# Sheet2.net
KiCad netlist of a schematic drawn in Altium Designer
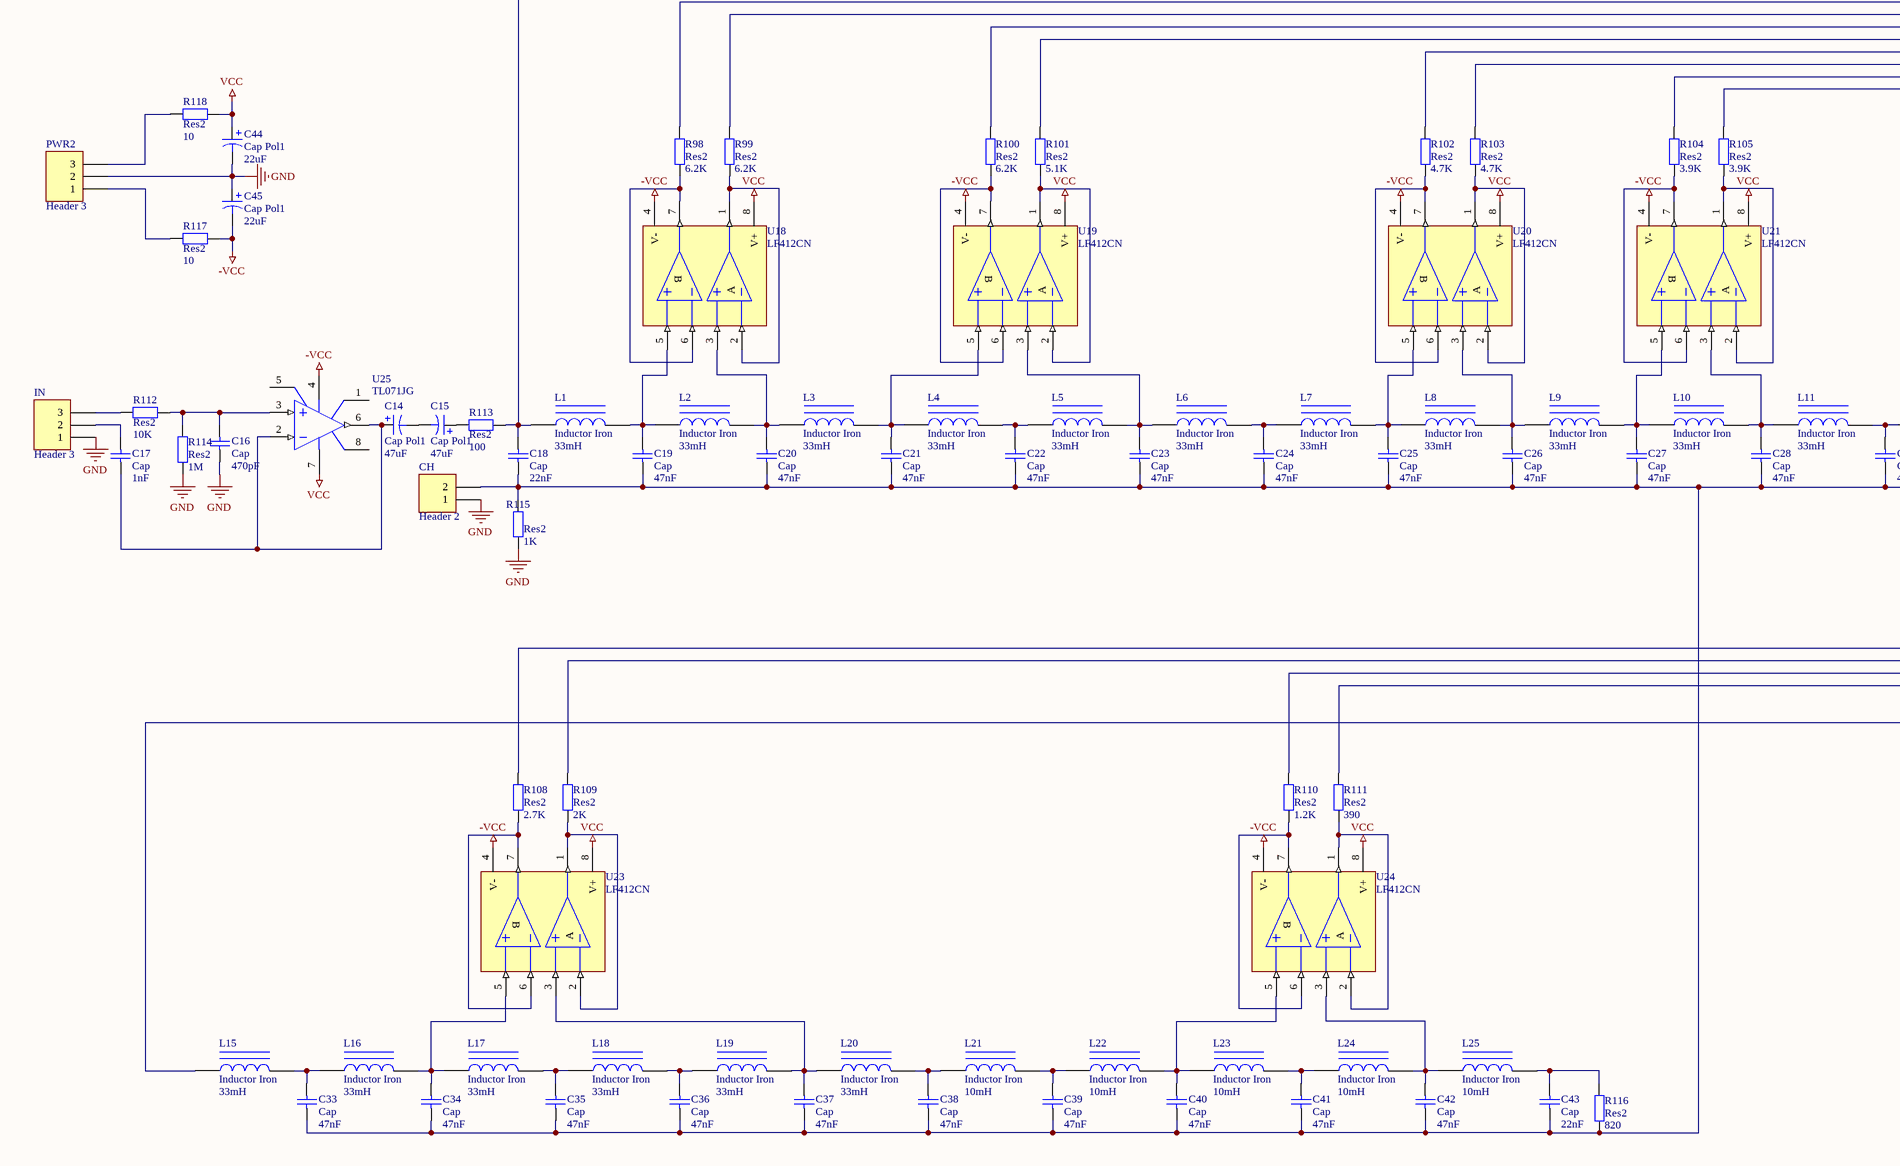
[diagram p0: Sheet2.SchDoc, left]
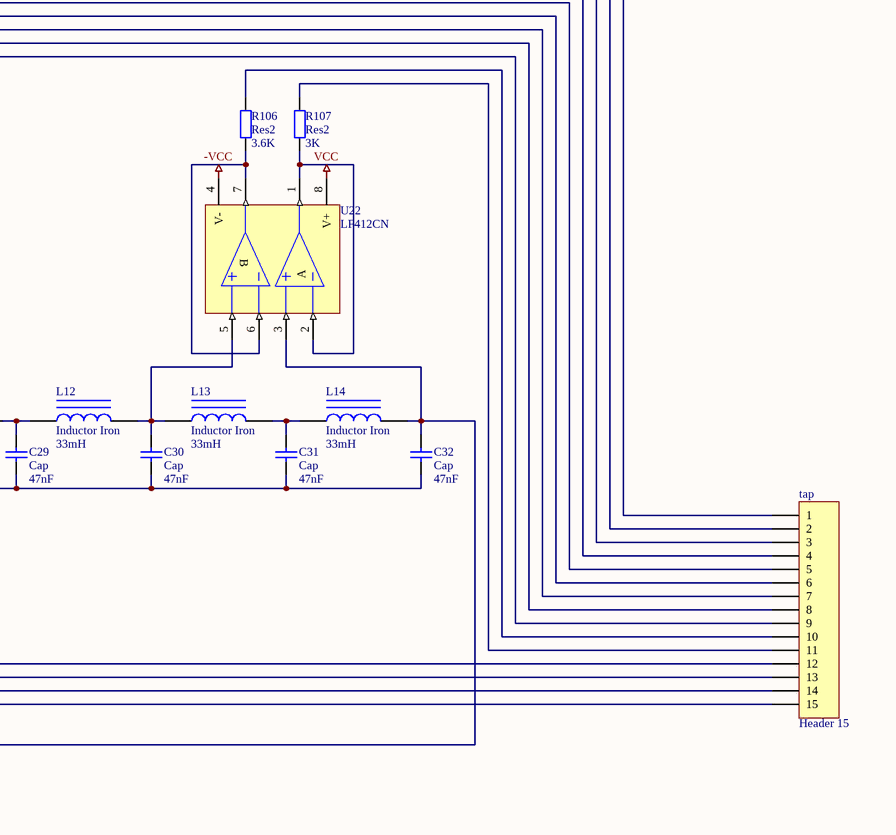
[diagram p1: Sheet2.SchDoc, right]

(export (version "E")
  (design (tool "Eeschema 10.0.6"))
  (components
    (comp (ref "C14")
      (value "Cap Pol1")
      (footprint "B")
      (description "Polarized Capacitor (Radial)")
      (fields (field (name "ALTIUM_VALUE") "47uF") (field (name "PUBLISHER") "Altium Limited"))
      (libsource (lib "Miscellaneous Devices") (part "Cap Pol1"))
    )
    (comp (ref "C15")
      (value "Cap Pol1")
      (footprint "B")
      (description "Polarized Capacitor (Radial)")
      (fields (field (name "ALTIUM_VALUE") "47uF") (field (name "PUBLISHER") "Altium Limited"))
      (libsource (lib "Miscellaneous Devices") (part "Cap Pol1"))
    )
    (comp (ref "C16")
      (value "Cap")
      (footprint "VP45-3.2")
      (description "Capacitor")
      (fields (field (name "ALTIUM_VALUE") "470pF") (field (name "PUBLISHER") "Altium Limited"))
      (libsource (lib "Miscellaneous Devices") (part "Cap"))
    )
    (comp (ref "C17")
      (value "Cap")
      (footprint "VP45-3.2")
      (description "Capacitor")
      (fields (field (name "ALTIUM_VALUE") "1nF") (field (name "PUBLISHER") "Altium Limited"))
      (libsource (lib "Miscellaneous Devices") (part "Cap"))
    )
    (comp (ref "C18")
      (value "Cap")
      (footprint "VP45-3.2")
      (description "Capacitor")
      (fields (field (name "ALTIUM_VALUE") "22nF") (field (name "PUBLISHER") "Altium Limited"))
      (libsource (lib "Miscellaneous Devices") (part "Cap"))
    )
    (comp (ref "C19")
      (value "Cap")
      (footprint "VP45-3.2")
      (description "Capacitor")
      (fields (field (name "ALTIUM_VALUE") "47nF") (field (name "PUBLISHER") "Altium Limited"))
      (libsource (lib "Miscellaneous Devices") (part "Cap"))
    )
    (comp (ref "C20")
      (value "Cap")
      (footprint "VP45-3.2")
      (description "Capacitor")
      (fields (field (name "ALTIUM_VALUE") "47nF") (field (name "PUBLISHER") "Altium Limited"))
      (libsource (lib "Miscellaneous Devices") (part "Cap"))
    )
    (comp (ref "C21")
      (value "Cap")
      (footprint "VP45-3.2")
      (description "Capacitor")
      (fields (field (name "ALTIUM_VALUE") "47nF") (field (name "PUBLISHER") "Altium Limited"))
      (libsource (lib "Miscellaneous Devices") (part "Cap"))
    )
    (comp (ref "C22")
      (value "Cap")
      (footprint "VP45-3.2")
      (description "Capacitor")
      (fields (field (name "ALTIUM_VALUE") "47nF") (field (name "PUBLISHER") "Altium Limited"))
      (libsource (lib "Miscellaneous Devices") (part "Cap"))
    )
    (comp (ref "C23")
      (value "Cap")
      (footprint "VP45-3.2")
      (description "Capacitor")
      (fields (field (name "ALTIUM_VALUE") "47nF") (field (name "PUBLISHER") "Altium Limited"))
      (libsource (lib "Miscellaneous Devices") (part "Cap"))
    )
    (comp (ref "C24")
      (value "Cap")
      (footprint "VP45-3.2")
      (description "Capacitor")
      (fields (field (name "ALTIUM_VALUE") "47nF") (field (name "PUBLISHER") "Altium Limited"))
      (libsource (lib "Miscellaneous Devices") (part "Cap"))
    )
    (comp (ref "C25")
      (value "Cap")
      (footprint "VP45-3.2")
      (description "Capacitor")
      (fields (field (name "ALTIUM_VALUE") "47nF") (field (name "PUBLISHER") "Altium Limited"))
      (libsource (lib "Miscellaneous Devices") (part "Cap"))
    )
    (comp (ref "C26")
      (value "Cap")
      (footprint "VP45-3.2")
      (description "Capacitor")
      (fields (field (name "ALTIUM_VALUE") "47nF") (field (name "PUBLISHER") "Altium Limited"))
      (libsource (lib "Miscellaneous Devices") (part "Cap"))
    )
    (comp (ref "C27")
      (value "Cap")
      (footprint "VP45-3.2")
      (description "Capacitor")
      (fields (field (name "ALTIUM_VALUE") "47nF") (field (name "PUBLISHER") "Altium Limited"))
      (libsource (lib "Miscellaneous Devices") (part "Cap"))
    )
    (comp (ref "C28")
      (value "Cap")
      (footprint "VP45-3.2")
      (description "Capacitor")
      (fields (field (name "ALTIUM_VALUE") "47nF") (field (name "PUBLISHER") "Altium Limited"))
      (libsource (lib "Miscellaneous Devices") (part "Cap"))
    )
    (comp (ref "C29")
      (value "Cap")
      (footprint "VP45-3.2")
      (description "Capacitor")
      (fields (field (name "ALTIUM_VALUE") "47nF") (field (name "PUBLISHER") "Altium Limited"))
      (libsource (lib "Miscellaneous Devices") (part "Cap"))
    )
    (comp (ref "C30")
      (value "Cap")
      (footprint "VP45-3.2")
      (description "Capacitor")
      (fields (field (name "ALTIUM_VALUE") "47nF") (field (name "PUBLISHER") "Altium Limited"))
      (libsource (lib "Miscellaneous Devices") (part "Cap"))
    )
    (comp (ref "C31")
      (value "Cap")
      (footprint "VP45-3.2")
      (description "Capacitor")
      (fields (field (name "ALTIUM_VALUE") "47nF") (field (name "PUBLISHER") "Altium Limited"))
      (libsource (lib "Miscellaneous Devices") (part "Cap"))
    )
    (comp (ref "C32")
      (value "Cap")
      (footprint "VP45-3.2")
      (description "Capacitor")
      (fields (field (name "ALTIUM_VALUE") "47nF") (field (name "PUBLISHER") "Altium Limited"))
      (libsource (lib "Miscellaneous Devices") (part "Cap"))
    )
    (comp (ref "C33")
      (value "Cap")
      (footprint "VP45-3.2")
      (description "Capacitor")
      (fields (field (name "ALTIUM_VALUE") "47nF") (field (name "PUBLISHER") "Altium Limited"))
      (libsource (lib "Miscellaneous Devices") (part "Cap"))
    )
    (comp (ref "C34")
      (value "Cap")
      (footprint "VP45-3.2")
      (description "Capacitor")
      (fields (field (name "ALTIUM_VALUE") "47nF") (field (name "PUBLISHER") "Altium Limited"))
      (libsource (lib "Miscellaneous Devices") (part "Cap"))
    )
    (comp (ref "C35")
      (value "Cap")
      (footprint "VP45-3.2")
      (description "Capacitor")
      (fields (field (name "ALTIUM_VALUE") "47nF") (field (name "PUBLISHER") "Altium Limited"))
      (libsource (lib "Miscellaneous Devices") (part "Cap"))
    )
    (comp (ref "C36")
      (value "Cap")
      (footprint "VP45-3.2")
      (description "Capacitor")
      (fields (field (name "ALTIUM_VALUE") "47nF") (field (name "PUBLISHER") "Altium Limited"))
      (libsource (lib "Miscellaneous Devices") (part "Cap"))
    )
    (comp (ref "C37")
      (value "Cap")
      (footprint "VP45-3.2")
      (description "Capacitor")
      (fields (field (name "ALTIUM_VALUE") "47nF") (field (name "PUBLISHER") "Altium Limited"))
      (libsource (lib "Miscellaneous Devices") (part "Cap"))
    )
    (comp (ref "C38")
      (value "Cap")
      (footprint "VP45-3.2")
      (description "Capacitor")
      (fields (field (name "ALTIUM_VALUE") "47nF") (field (name "PUBLISHER") "Altium Limited"))
      (libsource (lib "Miscellaneous Devices") (part "Cap"))
    )
    (comp (ref "C39")
      (value "Cap")
      (footprint "VP45-3.2")
      (description "Capacitor")
      (fields (field (name "ALTIUM_VALUE") "47nF") (field (name "PUBLISHER") "Altium Limited"))
      (libsource (lib "Miscellaneous Devices") (part "Cap"))
    )
    (comp (ref "C40")
      (value "Cap")
      (footprint "VP45-3.2")
      (description "Capacitor")
      (fields (field (name "ALTIUM_VALUE") "47nF") (field (name "PUBLISHER") "Altium Limited"))
      (libsource (lib "Miscellaneous Devices") (part "Cap"))
    )
    (comp (ref "C41")
      (value "Cap")
      (footprint "VP45-3.2")
      (description "Capacitor")
      (fields (field (name "ALTIUM_VALUE") "47nF") (field (name "PUBLISHER") "Altium Limited"))
      (libsource (lib "Miscellaneous Devices") (part "Cap"))
    )
    (comp (ref "C42")
      (value "Cap")
      (footprint "VP45-3.2")
      (description "Capacitor")
      (fields (field (name "ALTIUM_VALUE") "47nF") (field (name "PUBLISHER") "Altium Limited"))
      (libsource (lib "Miscellaneous Devices") (part "Cap"))
    )
    (comp (ref "C43")
      (value "Cap")
      (footprint "VP45-3.2")
      (description "Capacitor")
      (fields (field (name "ALTIUM_VALUE") "22nF") (field (name "PUBLISHER") "Altium Limited"))
      (libsource (lib "Miscellaneous Devices") (part "Cap"))
    )
    (comp (ref "C44")
      (value "Cap Pol1")
      (footprint "B")
      (description "Polarized Capacitor (Radial)")
      (fields (field (name "ALTIUM_VALUE") "22uF") (field (name "PUBLISHER") "Altium Limited"))
      (libsource (lib "Miscellaneous Devices") (part "Cap Pol1"))
    )
    (comp (ref "C45")
      (value "Cap Pol1")
      (footprint "B")
      (description "Polarized Capacitor (Radial)")
      (fields (field (name "ALTIUM_VALUE") "22uF") (field (name "PUBLISHER") "Altium Limited"))
      (libsource (lib "Miscellaneous Devices") (part "Cap Pol1"))
    )
    (comp (ref "CH")
      (value "Header 2")
      (footprint "HDR1X2")
      (description "Header, 2-Pin")
      (fields (field (name "PUBLISHER") "Altium Limited"))
      (libsource (lib "Miscellaneous Connectors") (part "Header 2"))
    )
    (comp (ref "IN")
      (value "Header 3")
      (footprint "HDR1X3")
      (description "Header, 3-Pin")
      (fields (field (name "PUBLISHER") "Altium Limited"))
      (libsource (lib "Miscellaneous Connectors") (part "Header 3"))
    )
    (comp (ref "L1")
      (value "Inductor Iron")
      (footprint "AXIAL-0.9")
      (description "Magnetic-Core Inductor")
      (fields (field (name "ALTIUM_VALUE") "33mH") (field (name "PUBLISHER") "Altium Limited"))
      (libsource (lib "Miscellaneous Devices") (part "Inductor Iron"))
    )
    (comp (ref "L2")
      (value "Inductor Iron")
      (footprint "AXIAL-0.9")
      (description "Magnetic-Core Inductor")
      (fields (field (name "ALTIUM_VALUE") "33mH") (field (name "PUBLISHER") "Altium Limited"))
      (libsource (lib "Miscellaneous Devices") (part "Inductor Iron"))
    )
    (comp (ref "L3")
      (value "Inductor Iron")
      (footprint "AXIAL-0.9")
      (description "Magnetic-Core Inductor")
      (fields (field (name "ALTIUM_VALUE") "33mH") (field (name "PUBLISHER") "Altium Limited"))
      (libsource (lib "Miscellaneous Devices") (part "Inductor Iron"))
    )
    (comp (ref "L4")
      (value "Inductor Iron")
      (footprint "AXIAL-0.9")
      (description "Magnetic-Core Inductor")
      (fields (field (name "ALTIUM_VALUE") "33mH") (field (name "PUBLISHER") "Altium Limited"))
      (libsource (lib "Miscellaneous Devices") (part "Inductor Iron"))
    )
    (comp (ref "L5")
      (value "Inductor Iron")
      (footprint "AXIAL-0.9")
      (description "Magnetic-Core Inductor")
      (fields (field (name "ALTIUM_VALUE") "33mH") (field (name "PUBLISHER") "Altium Limited"))
      (libsource (lib "Miscellaneous Devices") (part "Inductor Iron"))
    )
    (comp (ref "L6")
      (value "Inductor Iron")
      (footprint "AXIAL-0.9")
      (description "Magnetic-Core Inductor")
      (fields (field (name "ALTIUM_VALUE") "33mH") (field (name "PUBLISHER") "Altium Limited"))
      (libsource (lib "Miscellaneous Devices") (part "Inductor Iron"))
    )
    (comp (ref "L7")
      (value "Inductor Iron")
      (footprint "AXIAL-0.9")
      (description "Magnetic-Core Inductor")
      (fields (field (name "ALTIUM_VALUE") "33mH") (field (name "PUBLISHER") "Altium Limited"))
      (libsource (lib "Miscellaneous Devices") (part "Inductor Iron"))
    )
    (comp (ref "L8")
      (value "Inductor Iron")
      (footprint "AXIAL-0.9")
      (description "Magnetic-Core Inductor")
      (fields (field (name "ALTIUM_VALUE") "33mH") (field (name "PUBLISHER") "Altium Limited"))
      (libsource (lib "Miscellaneous Devices") (part "Inductor Iron"))
    )
    (comp (ref "L9")
      (value "Inductor Iron")
      (footprint "AXIAL-0.9")
      (description "Magnetic-Core Inductor")
      (fields (field (name "ALTIUM_VALUE") "33mH") (field (name "PUBLISHER") "Altium Limited"))
      (libsource (lib "Miscellaneous Devices") (part "Inductor Iron"))
    )
    (comp (ref "L10")
      (value "Inductor Iron")
      (footprint "AXIAL-0.9")
      (description "Magnetic-Core Inductor")
      (fields (field (name "ALTIUM_VALUE") "33mH") (field (name "PUBLISHER") "Altium Limited"))
      (libsource (lib "Miscellaneous Devices") (part "Inductor Iron"))
    )
    (comp (ref "L11")
      (value "Inductor Iron")
      (footprint "AXIAL-0.9")
      (description "Magnetic-Core Inductor")
      (fields (field (name "ALTIUM_VALUE") "33mH") (field (name "PUBLISHER") "Altium Limited"))
      (libsource (lib "Miscellaneous Devices") (part "Inductor Iron"))
    )
    (comp (ref "L12")
      (value "Inductor Iron")
      (footprint "AXIAL-0.9")
      (description "Magnetic-Core Inductor")
      (fields (field (name "ALTIUM_VALUE") "33mH") (field (name "PUBLISHER") "Altium Limited"))
      (libsource (lib "Miscellaneous Devices") (part "Inductor Iron"))
    )
    (comp (ref "L13")
      (value "Inductor Iron")
      (footprint "AXIAL-0.9")
      (description "Magnetic-Core Inductor")
      (fields (field (name "ALTIUM_VALUE") "33mH") (field (name "PUBLISHER") "Altium Limited"))
      (libsource (lib "Miscellaneous Devices") (part "Inductor Iron"))
    )
    (comp (ref "L14")
      (value "Inductor Iron")
      (footprint "AXIAL-0.9")
      (description "Magnetic-Core Inductor")
      (fields (field (name "ALTIUM_VALUE") "33mH") (field (name "PUBLISHER") "Altium Limited"))
      (libsource (lib "Miscellaneous Devices") (part "Inductor Iron"))
    )
    (comp (ref "L15")
      (value "Inductor Iron")
      (footprint "AXIAL-0.9")
      (description "Magnetic-Core Inductor")
      (fields (field (name "ALTIUM_VALUE") "33mH") (field (name "PUBLISHER") "Altium Limited"))
      (libsource (lib "Miscellaneous Devices") (part "Inductor Iron"))
    )
    (comp (ref "L16")
      (value "Inductor Iron")
      (footprint "AXIAL-0.9")
      (description "Magnetic-Core Inductor")
      (fields (field (name "ALTIUM_VALUE") "33mH") (field (name "PUBLISHER") "Altium Limited"))
      (libsource (lib "Miscellaneous Devices") (part "Inductor Iron"))
    )
    (comp (ref "L17")
      (value "Inductor Iron")
      (footprint "AXIAL-0.9")
      (description "Magnetic-Core Inductor")
      (fields (field (name "ALTIUM_VALUE") "33mH") (field (name "PUBLISHER") "Altium Limited"))
      (libsource (lib "Miscellaneous Devices") (part "Inductor Iron"))
    )
    (comp (ref "L18")
      (value "Inductor Iron")
      (footprint "AXIAL-0.9")
      (description "Magnetic-Core Inductor")
      (fields (field (name "ALTIUM_VALUE") "33mH") (field (name "PUBLISHER") "Altium Limited"))
      (libsource (lib "Miscellaneous Devices") (part "Inductor Iron"))
    )
    (comp (ref "L19")
      (value "Inductor Iron")
      (footprint "AXIAL-0.9")
      (description "Magnetic-Core Inductor")
      (fields (field (name "ALTIUM_VALUE") "33mH") (field (name "PUBLISHER") "Altium Limited"))
      (libsource (lib "Miscellaneous Devices") (part "Inductor Iron"))
    )
    (comp (ref "L20")
      (value "Inductor Iron")
      (footprint "AXIAL-0.9")
      (description "Magnetic-Core Inductor")
      (fields (field (name "ALTIUM_VALUE") "33mH") (field (name "PUBLISHER") "Altium Limited"))
      (libsource (lib "Miscellaneous Devices") (part "Inductor Iron"))
    )
    (comp (ref "L21")
      (value "Inductor Iron")
      (footprint "AXIAL-0.9")
      (description "Magnetic-Core Inductor")
      (fields (field (name "ALTIUM_VALUE") "10mH") (field (name "PUBLISHER") "Altium Limited"))
      (libsource (lib "Miscellaneous Devices") (part "Inductor Iron"))
    )
    (comp (ref "L22")
      (value "Inductor Iron")
      (footprint "AXIAL-0.9")
      (description "Magnetic-Core Inductor")
      (fields (field (name "ALTIUM_VALUE") "10mH") (field (name "PUBLISHER") "Altium Limited"))
      (libsource (lib "Miscellaneous Devices") (part "Inductor Iron"))
    )
    (comp (ref "L23")
      (value "Inductor Iron")
      (footprint "AXIAL-0.9")
      (description "Magnetic-Core Inductor")
      (fields (field (name "ALTIUM_VALUE") "10mH") (field (name "PUBLISHER") "Altium Limited"))
      (libsource (lib "Miscellaneous Devices") (part "Inductor Iron"))
    )
    (comp (ref "L24")
      (value "Inductor Iron")
      (footprint "AXIAL-0.9")
      (description "Magnetic-Core Inductor")
      (fields (field (name "ALTIUM_VALUE") "10mH") (field (name "PUBLISHER") "Altium Limited"))
      (libsource (lib "Miscellaneous Devices") (part "Inductor Iron"))
    )
    (comp (ref "L25")
      (value "Inductor Iron")
      (footprint "AXIAL-0.9")
      (description "Magnetic-Core Inductor")
      (fields (field (name "ALTIUM_VALUE") "10mH") (field (name "PUBLISHER") "Altium Limited"))
      (libsource (lib "Miscellaneous Devices") (part "Inductor Iron"))
    )
    (comp (ref "PWR2")
      (value "Header 3")
      (footprint "HDR1X3")
      (description "Header, 3-Pin")
      (fields (field (name "PUBLISHER") "Altium Limited"))
      (libsource (lib "Miscellaneous Connectors") (part "Header 3"))
    )
    (comp (ref "R98")
      (value "Res2")
      (footprint "AXIAL-0.4")
      (description "Resistor")
      (fields (field (name "ALTIUM_VALUE") "6.2K") (field (name "PUBLISHER") "Altium Limited"))
      (libsource (lib "") (part "Res2_1"))
    )
    (comp (ref "R99")
      (value "Res2")
      (footprint "AXIAL-0.4")
      (description "Resistor")
      (fields (field (name "ALTIUM_VALUE") "6.2K") (field (name "PUBLISHER") "Altium Limited"))
      (libsource (lib "") (part "Res2_1"))
    )
    (comp (ref "R100")
      (value "Res2")
      (footprint "AXIAL-0.4")
      (description "Resistor")
      (fields (field (name "ALTIUM_VALUE") "6.2K") (field (name "PUBLISHER") "Altium Limited"))
      (libsource (lib "") (part "Res2_1"))
    )
    (comp (ref "R101")
      (value "Res2")
      (footprint "AXIAL-0.4")
      (description "Resistor")
      (fields (field (name "ALTIUM_VALUE") "5.1K") (field (name "PUBLISHER") "Altium Limited"))
      (libsource (lib "") (part "Res2_1"))
    )
    (comp (ref "R102")
      (value "Res2")
      (footprint "AXIAL-0.4")
      (description "Resistor")
      (fields (field (name "ALTIUM_VALUE") "4.7K") (field (name "PUBLISHER") "Altium Limited"))
      (libsource (lib "") (part "Res2_1"))
    )
    (comp (ref "R103")
      (value "Res2")
      (footprint "AXIAL-0.4")
      (description "Resistor")
      (fields (field (name "ALTIUM_VALUE") "4.7K") (field (name "PUBLISHER") "Altium Limited"))
      (libsource (lib "") (part "Res2_1"))
    )
    (comp (ref "R104")
      (value "Res2")
      (footprint "AXIAL-0.4")
      (description "Resistor")
      (fields (field (name "ALTIUM_VALUE") "3.9K") (field (name "PUBLISHER") "Altium Limited"))
      (libsource (lib "") (part "Res2_1"))
    )
    (comp (ref "R105")
      (value "Res2")
      (footprint "AXIAL-0.4")
      (description "Resistor")
      (fields (field (name "ALTIUM_VALUE") "3.9K") (field (name "PUBLISHER") "Altium Limited"))
      (libsource (lib "") (part "Res2_1"))
    )
    (comp (ref "R106")
      (value "Res2")
      (footprint "AXIAL-0.4")
      (description "Resistor")
      (fields (field (name "ALTIUM_VALUE") "3.6K") (field (name "PUBLISHER") "Altium Limited"))
      (libsource (lib "") (part "Res2_1"))
    )
    (comp (ref "R107")
      (value "Res2")
      (footprint "AXIAL-0.4")
      (description "Resistor")
      (fields (field (name "ALTIUM_VALUE") "3K") (field (name "PUBLISHER") "Altium Limited"))
      (libsource (lib "") (part "Res2_1"))
    )
    (comp (ref "R108")
      (value "Res2")
      (footprint "AXIAL-0.4")
      (description "Resistor")
      (fields (field (name "ALTIUM_VALUE") "2.7K") (field (name "PUBLISHER") "Altium Limited"))
      (libsource (lib "") (part "Res2_1"))
    )
    (comp (ref "R109")
      (value "Res2")
      (footprint "AXIAL-0.4")
      (description "Resistor")
      (fields (field (name "ALTIUM_VALUE") "2K") (field (name "PUBLISHER") "Altium Limited"))
      (libsource (lib "") (part "Res2_1"))
    )
    (comp (ref "R110")
      (value "Res2")
      (footprint "AXIAL-0.4")
      (description "Resistor")
      (fields (field (name "ALTIUM_VALUE") "1.2K") (field (name "PUBLISHER") "Altium Limited"))
      (libsource (lib "") (part "Res2_1"))
    )
    (comp (ref "R111")
      (value "Res2")
      (footprint "AXIAL-0.4")
      (description "Resistor")
      (fields (field (name "ALTIUM_VALUE") "390") (field (name "PUBLISHER") "Altium Limited"))
      (libsource (lib "") (part "Res2_1"))
    )
    (comp (ref "R112")
      (value "Res2")
      (footprint "AXIAL-0.4")
      (description "Resistor")
      (fields (field (name "ALTIUM_VALUE") "10K") (field (name "PUBLISHER") "Altium Limited"))
      (libsource (lib "Miscellaneous Devices") (part "Res2"))
    )
    (comp (ref "R113")
      (value "Res2")
      (footprint "AXIAL-0.4")
      (description "Resistor")
      (fields (field (name "ALTIUM_VALUE") "100") (field (name "PUBLISHER") "Altium Limited"))
      (libsource (lib "") (part "Res2_2"))
    )
    (comp (ref "R114")
      (value "Res2")
      (footprint "AXIAL-0.4")
      (description "Resistor")
      (fields (field (name "ALTIUM_VALUE") "1M") (field (name "PUBLISHER") "Altium Limited"))
      (libsource (lib "") (part "Res2_1"))
    )
    (comp (ref "R115")
      (value "Res2")
      (footprint "AXIAL-0.4")
      (description "Resistor")
      (fields (field (name "ALTIUM_VALUE") "1K") (field (name "PUBLISHER") "Altium Limited"))
      (libsource (lib "") (part "Res2_1"))
    )
    (comp (ref "R116")
      (value "Res2")
      (footprint "AXIAL-0.4")
      (description "Resistor")
      (fields (field (name "ALTIUM_VALUE") "820") (field (name "PUBLISHER") "Altium Limited"))
      (libsource (lib "") (part "Res2_1"))
    )
    (comp (ref "R117")
      (value "Res2")
      (footprint "AXIAL-0.4")
      (description "Resistor")
      (fields (field (name "ALTIUM_VALUE") "10") (field (name "PUBLISHER") "Altium Limited"))
      (libsource (lib "Miscellaneous Devices") (part "Res2"))
    )
    (comp (ref "R118")
      (value "Res2")
      (footprint "AXIAL-0.4")
      (description "Resistor")
      (fields (field (name "ALTIUM_VALUE") "10") (field (name "PUBLISHER") "Altium Limited"))
      (libsource (lib "Miscellaneous Devices") (part "Res2"))
    )
    (comp (ref "tap")
      (value "Header 15")
      (footprint "HDR1X15")
      (description "Header, 15-Pin")
      (fields (field (name "PUBLISHER") "Altium Limited"))
      (libsource (lib "Miscellaneous Connectors") (part "Header 15"))
    )
    (comp (ref "U18")
      (value "LF412CN")
      (footprint "N08E")
      (description "Low Offset, Low Drift Dual JFET Input Operational Amplifier")
      (fields
        (field (name "MANUFACTURER") "National Semiconductor")
        (field (name "DIGIKEYPARTNUMBER") "LF412CN-ND")
        (field (name "PUBLISHER") "Altium Limited")
      )
      (libsource (lib "NSC Amplifier") (part "LF412CN"))
    )
    (comp (ref "U19")
      (value "LF412CN")
      (footprint "N08E")
      (description "Low Offset, Low Drift Dual JFET Input Operational Amplifier")
      (fields
        (field (name "MANUFACTURER") "National Semiconductor")
        (field (name "DIGIKEYPARTNUMBER") "LF412CN-ND")
        (field (name "PUBLISHER") "Altium Limited")
      )
      (libsource (lib "NSC Amplifier") (part "LF412CN"))
    )
    (comp (ref "U20")
      (value "LF412CN")
      (footprint "N08E")
      (description "Low Offset, Low Drift Dual JFET Input Operational Amplifier")
      (fields
        (field (name "MANUFACTURER") "National Semiconductor")
        (field (name "DIGIKEYPARTNUMBER") "LF412CN-ND")
        (field (name "PUBLISHER") "Altium Limited")
      )
      (libsource (lib "NSC Amplifier") (part "LF412CN"))
    )
    (comp (ref "U21")
      (value "LF412CN")
      (footprint "N08E")
      (description "Low Offset, Low Drift Dual JFET Input Operational Amplifier")
      (fields
        (field (name "MANUFACTURER") "National Semiconductor")
        (field (name "DIGIKEYPARTNUMBER") "LF412CN-ND")
        (field (name "PUBLISHER") "Altium Limited")
      )
      (libsource (lib "NSC Amplifier") (part "LF412CN"))
    )
    (comp (ref "U22")
      (value "LF412CN")
      (footprint "N08E")
      (description "Low Offset, Low Drift Dual JFET Input Operational Amplifier")
      (fields
        (field (name "MANUFACTURER") "National Semiconductor")
        (field (name "DIGIKEYPARTNUMBER") "LF412CN-ND")
        (field (name "PUBLISHER") "Altium Limited")
      )
      (libsource (lib "NSC Amplifier") (part "LF412CN"))
    )
    (comp (ref "U23")
      (value "LF412CN")
      (footprint "N08E")
      (description "Low Offset, Low Drift Dual JFET Input Operational Amplifier")
      (fields
        (field (name "MANUFACTURER") "National Semiconductor")
        (field (name "DIGIKEYPARTNUMBER") "LF412CN-ND")
        (field (name "PUBLISHER") "Altium Limited")
      )
      (libsource (lib "NSC Amplifier") (part "LF412CN"))
    )
    (comp (ref "U24")
      (value "LF412CN")
      (footprint "N08E")
      (description "Low Offset, Low Drift Dual JFET Input Operational Amplifier")
      (fields
        (field (name "MANUFACTURER") "National Semiconductor")
        (field (name "DIGIKEYPARTNUMBER") "LF412CN-ND")
        (field (name "PUBLISHER") "Altium Limited")
      )
      (libsource (lib "NSC Amplifier") (part "LF412CN"))
    )
    (comp (ref "U25")
      (value "TL071JG")
      (footprint "JG008")
      (description "Low-Noise JFET-Input Operational Amplifier")
      (fields (field (name "PUBLISHER") "Altium Limited"))
      (libsource (lib "TI Operational Amplifier") (part "TL071JG"))
    )
  )
  (nets
    (net (code "1") (name "-VCC") (class "Default")
      (node (ref "C45") (pin "2") (pinfunction "2_2") (pintype "passive"))
      (node (ref "R117") (pin "1") (pinfunction "1_1") (pintype "passive"))
      (node (ref "U18") (pin "4") (pinfunction "V-_4") (pintype "power_in"))
      (node (ref "U19") (pin "4") (pinfunction "V-_4") (pintype "power_in"))
      (node (ref "U20") (pin "4") (pinfunction "V-_4") (pintype "power_in"))
      (node (ref "U21") (pin "4") (pinfunction "V-_4") (pintype "power_in"))
      (node (ref "U22") (pin "4") (pinfunction "V-_4") (pintype "power_in"))
      (node (ref "U23") (pin "4") (pinfunction "V-_4") (pintype "power_in"))
      (node (ref "U24") (pin "4") (pinfunction "V-_4") (pintype "power_in"))
      (node (ref "U25") (pin "4") (pinfunction "V-_4") (pintype "power_in"))
    )
    (net (code "2") (name "GND") (class "Default")
      (node (ref "C16") (pin "1") (pinfunction "1_1") (pintype "passive"))
      (node (ref "C44") (pin "2") (pinfunction "2_2") (pintype "passive"))
      (node (ref "C45") (pin "1") (pinfunction "1_1") (pintype "passive"))
      (node (ref "CH") (pin "1") (pinfunction "1_1") (pintype "passive"))
      (node (ref "IN") (pin "1") (pinfunction "1_1") (pintype "passive"))
      (node (ref "PWR2") (pin "2") (pinfunction "2_2") (pintype "passive"))
      (node (ref "R114") (pin "1") (pinfunction "1_1") (pintype "passive"))
      (node (ref "R115") (pin "1") (pinfunction "1_1") (pintype "passive"))
    )
    (net (code "3") (name "Net-(C14-Pad2)") (class "Default")
      (node (ref "C14") (pin "2") (pinfunction "2_2") (pintype "passive"))
      (node (ref "C15") (pin "2") (pinfunction "2_2") (pintype "passive"))
    )
    (net (code "4") (name "Net-(C15-Pad1)") (class "Default")
      (node (ref "C15") (pin "1") (pinfunction "1_1") (pintype "passive"))
      (node (ref "R113") (pin "1") (pinfunction "1_1") (pintype "passive"))
    )
    (net (code "5") (name "Net-(C17-Pad2)") (class "Default")
      (node (ref "C17") (pin "2") (pinfunction "2_2") (pintype "passive"))
      (node (ref "IN") (pin "2") (pinfunction "2_2") (pintype "passive"))
    )
    (net (code "6") (name "Net-(C18-Pad1)") (class "Default")
      (node (ref "C18") (pin "1") (pinfunction "1_1") (pintype "passive"))
      (node (ref "C19") (pin "1") (pinfunction "1_1") (pintype "passive"))
      (node (ref "C20") (pin "1") (pinfunction "1_1") (pintype "passive"))
      (node (ref "C21") (pin "1") (pinfunction "1_1") (pintype "passive"))
      (node (ref "C22") (pin "1") (pinfunction "1_1") (pintype "passive"))
      (node (ref "C23") (pin "1") (pinfunction "1_1") (pintype "passive"))
      (node (ref "C24") (pin "1") (pinfunction "1_1") (pintype "passive"))
      (node (ref "C25") (pin "1") (pinfunction "1_1") (pintype "passive"))
      (node (ref "C26") (pin "1") (pinfunction "1_1") (pintype "passive"))
      (node (ref "C27") (pin "1") (pinfunction "1_1") (pintype "passive"))
      (node (ref "C28") (pin "1") (pinfunction "1_1") (pintype "passive"))
      (node (ref "C29") (pin "1") (pinfunction "1_1") (pintype "passive"))
      (node (ref "C30") (pin "1") (pinfunction "1_1") (pintype "passive"))
      (node (ref "C31") (pin "1") (pinfunction "1_1") (pintype "passive"))
      (node (ref "C32") (pin "1") (pinfunction "1_1") (pintype "passive"))
      (node (ref "C33") (pin "1") (pinfunction "1_1") (pintype "passive"))
      (node (ref "C34") (pin "1") (pinfunction "1_1") (pintype "passive"))
      (node (ref "C35") (pin "1") (pinfunction "1_1") (pintype "passive"))
      (node (ref "C36") (pin "1") (pinfunction "1_1") (pintype "passive"))
      (node (ref "C37") (pin "1") (pinfunction "1_1") (pintype "passive"))
      (node (ref "C38") (pin "1") (pinfunction "1_1") (pintype "passive"))
      (node (ref "C39") (pin "1") (pinfunction "1_1") (pintype "passive"))
      (node (ref "C40") (pin "1") (pinfunction "1_1") (pintype "passive"))
      (node (ref "C41") (pin "1") (pinfunction "1_1") (pintype "passive"))
      (node (ref "C42") (pin "1") (pinfunction "1_1") (pintype "passive"))
      (node (ref "C43") (pin "1") (pinfunction "1_1") (pintype "passive"))
      (node (ref "CH") (pin "2") (pinfunction "2_2") (pintype "passive"))
      (node (ref "R115") (pin "2") (pinfunction "2_2") (pintype "passive"))
      (node (ref "R116") (pin "1") (pinfunction "1_1") (pintype "passive"))
    )
    (net (code "7") (name "Net-(C18-Pad2)") (class "Default")
      (node (ref "C18") (pin "2") (pinfunction "2_2") (pintype "passive"))
      (node (ref "L1") (pin "1") (pinfunction "1_1") (pintype "passive"))
      (node (ref "R113") (pin "2") (pinfunction "2_2") (pintype "passive"))
      (node (ref "tap") (pin "1") (pinfunction "1_1") (pintype "passive"))
    )
    (net (code "8") (name "Net-(C22-Pad2)") (class "Default")
      (node (ref "C22") (pin "2") (pinfunction "2_2") (pintype "passive"))
      (node (ref "L4") (pin "2") (pinfunction "2_2") (pintype "passive"))
      (node (ref "L5") (pin "1") (pinfunction "1_1") (pintype "passive"))
    )
    (net (code "9") (name "Net-(C24-Pad2)") (class "Default")
      (node (ref "C24") (pin "2") (pinfunction "2_2") (pintype "passive"))
      (node (ref "L6") (pin "2") (pinfunction "2_2") (pintype "passive"))
      (node (ref "L7") (pin "1") (pinfunction "1_1") (pintype "passive"))
    )
    (net (code "10") (name "Net-(C29-Pad2)") (class "Default")
      (node (ref "C29") (pin "2") (pinfunction "2_2") (pintype "passive"))
      (node (ref "L11") (pin "2") (pinfunction "2_2") (pintype "passive"))
      (node (ref "L12") (pin "1") (pinfunction "1_1") (pintype "passive"))
    )
    (net (code "11") (name "Net-(C31-Pad2)") (class "Default")
      (node (ref "C31") (pin "2") (pinfunction "2_2") (pintype "passive"))
      (node (ref "L13") (pin "2") (pinfunction "2_2") (pintype "passive"))
      (node (ref "L14") (pin "1") (pinfunction "1_1") (pintype "passive"))
    )
    (net (code "12") (name "Net-(C33-Pad2)") (class "Default")
      (node (ref "C33") (pin "2") (pinfunction "2_2") (pintype "passive"))
      (node (ref "L15") (pin "2") (pinfunction "2_2") (pintype "passive"))
      (node (ref "L16") (pin "1") (pinfunction "1_1") (pintype "passive"))
    )
    (net (code "13") (name "Net-(C35-Pad2)") (class "Default")
      (node (ref "C35") (pin "2") (pinfunction "2_2") (pintype "passive"))
      (node (ref "L17") (pin "2") (pinfunction "2_2") (pintype "passive"))
      (node (ref "L18") (pin "1") (pinfunction "1_1") (pintype "passive"))
    )
    (net (code "14") (name "Net-(C36-Pad2)") (class "Default")
      (node (ref "C36") (pin "2") (pinfunction "2_2") (pintype "passive"))
      (node (ref "L18") (pin "2") (pinfunction "2_2") (pintype "passive"))
      (node (ref "L19") (pin "1") (pinfunction "1_1") (pintype "passive"))
    )
    (net (code "15") (name "Net-(C38-Pad2)") (class "Default")
      (node (ref "C38") (pin "2") (pinfunction "2_2") (pintype "passive"))
      (node (ref "L20") (pin "2") (pinfunction "2_2") (pintype "passive"))
      (node (ref "L21") (pin "1") (pinfunction "1_1") (pintype "passive"))
    )
    (net (code "16") (name "Net-(C39-Pad2)") (class "Default")
      (node (ref "C39") (pin "2") (pinfunction "2_2") (pintype "passive"))
      (node (ref "L21") (pin "2") (pinfunction "2_2") (pintype "passive"))
      (node (ref "L22") (pin "1") (pinfunction "1_1") (pintype "passive"))
    )
    (net (code "17") (name "Net-(C41-Pad2)") (class "Default")
      (node (ref "C41") (pin "2") (pinfunction "2_2") (pintype "passive"))
      (node (ref "L23") (pin "2") (pinfunction "2_2") (pintype "passive"))
      (node (ref "L24") (pin "1") (pinfunction "1_1") (pintype "passive"))
    )
    (net (code "18") (name "Net-(C43-Pad2)") (class "Default")
      (node (ref "C43") (pin "2") (pinfunction "2_2") (pintype "passive"))
      (node (ref "L25") (pin "2") (pinfunction "2_2") (pintype "passive"))
      (node (ref "R116") (pin "2") (pinfunction "2_2") (pintype "passive"))
    )
    (net (code "19") (name "Net-(IN-Pad3)") (class "Default")
      (node (ref "IN") (pin "3") (pinfunction "3_3") (pintype "passive"))
      (node (ref "R112") (pin "2") (pinfunction "2_2") (pintype "passive"))
    )
    (net (code "20") (name "Net-(PWR2-Pad1)") (class "Default")
      (node (ref "PWR2") (pin "1") (pinfunction "1_1") (pintype "passive"))
      (node (ref "R117") (pin "2") (pinfunction "2_2") (pintype "passive"))
    )
    (net (code "21") (name "Net-(PWR2-Pad3)") (class "Default")
      (node (ref "PWR2") (pin "3") (pinfunction "3_3") (pintype "passive"))
      (node (ref "R118") (pin "2") (pinfunction "2_2") (pintype "passive"))
    )
    (net (code "22") (name "Net-(R98-Pad2)") (class "Default")
      (node (ref "R98") (pin "2") (pinfunction "2_2") (pintype "passive"))
      (node (ref "tap") (pin "2") (pinfunction "2_2") (pintype "passive"))
    )
    (net (code "23") (name "Net-(R99-Pad2)") (class "Default")
      (node (ref "R99") (pin "2") (pinfunction "2_2") (pintype "passive"))
      (node (ref "tap") (pin "3") (pinfunction "3_3") (pintype "passive"))
    )
    (net (code "24") (name "Net-(R100-Pad2)") (class "Default")
      (node (ref "R100") (pin "2") (pinfunction "2_2") (pintype "passive"))
      (node (ref "tap") (pin "4") (pinfunction "4_4") (pintype "passive"))
    )
    (net (code "25") (name "Net-(R101-Pad2)") (class "Default")
      (node (ref "R101") (pin "2") (pinfunction "2_2") (pintype "passive"))
      (node (ref "tap") (pin "5") (pinfunction "5_5") (pintype "passive"))
    )
    (net (code "26") (name "Net-(R102-Pad2)") (class "Default")
      (node (ref "R102") (pin "2") (pinfunction "2_2") (pintype "passive"))
      (node (ref "tap") (pin "6") (pinfunction "6_6") (pintype "passive"))
    )
    (net (code "27") (name "Net-(R103-Pad2)") (class "Default")
      (node (ref "R103") (pin "2") (pinfunction "2_2") (pintype "passive"))
      (node (ref "tap") (pin "7") (pinfunction "7_7") (pintype "passive"))
    )
    (net (code "28") (name "Net-(R104-Pad2)") (class "Default")
      (node (ref "R104") (pin "2") (pinfunction "2_2") (pintype "passive"))
      (node (ref "tap") (pin "8") (pinfunction "8_8") (pintype "passive"))
    )
    (net (code "29") (name "Net-(R105-Pad2)") (class "Default")
      (node (ref "R105") (pin "2") (pinfunction "2_2") (pintype "passive"))
      (node (ref "tap") (pin "9") (pinfunction "9_9") (pintype "passive"))
    )
    (net (code "30") (name "Net-(R106-Pad2)") (class "Default")
      (node (ref "R106") (pin "2") (pinfunction "2_2") (pintype "passive"))
      (node (ref "tap") (pin "10") (pinfunction "10_10") (pintype "passive"))
    )
    (net (code "31") (name "Net-(R107-Pad2)") (class "Default")
      (node (ref "R107") (pin "2") (pinfunction "2_2") (pintype "passive"))
      (node (ref "tap") (pin "11") (pinfunction "11_11") (pintype "passive"))
    )
    (net (code "32") (name "Net-(R108-Pad2)") (class "Default")
      (node (ref "R108") (pin "2") (pinfunction "2_2") (pintype "passive"))
      (node (ref "tap") (pin "12") (pinfunction "12_12") (pintype "passive"))
    )
    (net (code "33") (name "Net-(R109-Pad2)") (class "Default")
      (node (ref "R109") (pin "2") (pinfunction "2_2") (pintype "passive"))
      (node (ref "tap") (pin "13") (pinfunction "13_13") (pintype "passive"))
    )
    (net (code "34") (name "Net-(R110-Pad2)") (class "Default")
      (node (ref "R110") (pin "2") (pinfunction "2_2") (pintype "passive"))
      (node (ref "tap") (pin "14") (pinfunction "14_14") (pintype "passive"))
    )
    (net (code "35") (name "Net-(R111-Pad2)") (class "Default")
      (node (ref "R111") (pin "2") (pinfunction "2_2") (pintype "passive"))
      (node (ref "tap") (pin "15") (pinfunction "15_15") (pintype "passive"))
    )
    (net (code "36") (name "Net-(U18-INA+)") (class "Default")
      (node (ref "C20") (pin "2") (pinfunction "2_2") (pintype "passive"))
      (node (ref "L2") (pin "2") (pinfunction "2_2") (pintype "passive"))
      (node (ref "L3") (pin "1") (pinfunction "1_1") (pintype "passive"))
      (node (ref "U18") (pin "3") (pinfunction "INA+_3") (pintype "input"))
    )
    (net (code "37") (name "Net-(U18-INA-)") (class "Default")
      (node (ref "R99") (pin "1") (pinfunction "1_1") (pintype "passive"))
      (node (ref "U18") (pin "1") (pinfunction "OUTA_1") (pintype "output"))
      (node (ref "U18") (pin "2") (pinfunction "INA-_2") (pintype "input"))
    )
    (net (code "38") (name "Net-(U18-INB+)") (class "Default")
      (node (ref "C19") (pin "2") (pinfunction "2_2") (pintype "passive"))
      (node (ref "L1") (pin "2") (pinfunction "2_2") (pintype "passive"))
      (node (ref "L2") (pin "1") (pinfunction "1_1") (pintype "passive"))
      (node (ref "U18") (pin "5") (pinfunction "INB+_5") (pintype "input"))
    )
    (net (code "39") (name "Net-(U18-INB-)") (class "Default")
      (node (ref "R98") (pin "1") (pinfunction "1_1") (pintype "passive"))
      (node (ref "U18") (pin "6") (pinfunction "INB-_6") (pintype "input"))
      (node (ref "U18") (pin "7") (pinfunction "OUTB_7") (pintype "output"))
    )
    (net (code "40") (name "Net-(U19-INA+)") (class "Default")
      (node (ref "C23") (pin "2") (pinfunction "2_2") (pintype "passive"))
      (node (ref "L5") (pin "2") (pinfunction "2_2") (pintype "passive"))
      (node (ref "L6") (pin "1") (pinfunction "1_1") (pintype "passive"))
      (node (ref "U19") (pin "3") (pinfunction "INA+_3") (pintype "input"))
    )
    (net (code "41") (name "Net-(U19-INA-)") (class "Default")
      (node (ref "R101") (pin "1") (pinfunction "1_1") (pintype "passive"))
      (node (ref "U19") (pin "1") (pinfunction "OUTA_1") (pintype "output"))
      (node (ref "U19") (pin "2") (pinfunction "INA-_2") (pintype "input"))
    )
    (net (code "42") (name "Net-(U19-INB+)") (class "Default")
      (node (ref "C21") (pin "2") (pinfunction "2_2") (pintype "passive"))
      (node (ref "L3") (pin "2") (pinfunction "2_2") (pintype "passive"))
      (node (ref "L4") (pin "1") (pinfunction "1_1") (pintype "passive"))
      (node (ref "U19") (pin "5") (pinfunction "INB+_5") (pintype "input"))
    )
    (net (code "43") (name "Net-(U19-INB-)") (class "Default")
      (node (ref "R100") (pin "1") (pinfunction "1_1") (pintype "passive"))
      (node (ref "U19") (pin "6") (pinfunction "INB-_6") (pintype "input"))
      (node (ref "U19") (pin "7") (pinfunction "OUTB_7") (pintype "output"))
    )
    (net (code "44") (name "Net-(U20-INA+)") (class "Default")
      (node (ref "C26") (pin "2") (pinfunction "2_2") (pintype "passive"))
      (node (ref "L8") (pin "2") (pinfunction "2_2") (pintype "passive"))
      (node (ref "L9") (pin "1") (pinfunction "1_1") (pintype "passive"))
      (node (ref "U20") (pin "3") (pinfunction "INA+_3") (pintype "input"))
    )
    (net (code "45") (name "Net-(U20-INA-)") (class "Default")
      (node (ref "R103") (pin "1") (pinfunction "1_1") (pintype "passive"))
      (node (ref "U20") (pin "1") (pinfunction "OUTA_1") (pintype "output"))
      (node (ref "U20") (pin "2") (pinfunction "INA-_2") (pintype "input"))
    )
    (net (code "46") (name "Net-(U20-INB+)") (class "Default")
      (node (ref "C25") (pin "2") (pinfunction "2_2") (pintype "passive"))
      (node (ref "L7") (pin "2") (pinfunction "2_2") (pintype "passive"))
      (node (ref "L8") (pin "1") (pinfunction "1_1") (pintype "passive"))
      (node (ref "U20") (pin "5") (pinfunction "INB+_5") (pintype "input"))
    )
    (net (code "47") (name "Net-(U20-INB-)") (class "Default")
      (node (ref "R102") (pin "1") (pinfunction "1_1") (pintype "passive"))
      (node (ref "U20") (pin "6") (pinfunction "INB-_6") (pintype "input"))
      (node (ref "U20") (pin "7") (pinfunction "OUTB_7") (pintype "output"))
    )
    (net (code "48") (name "Net-(U21-INA+)") (class "Default")
      (node (ref "C28") (pin "2") (pinfunction "2_2") (pintype "passive"))
      (node (ref "L10") (pin "2") (pinfunction "2_2") (pintype "passive"))
      (node (ref "L11") (pin "1") (pinfunction "1_1") (pintype "passive"))
      (node (ref "U21") (pin "3") (pinfunction "INA+_3") (pintype "input"))
    )
    (net (code "49") (name "Net-(U21-INA-)") (class "Default")
      (node (ref "R105") (pin "1") (pinfunction "1_1") (pintype "passive"))
      (node (ref "U21") (pin "1") (pinfunction "OUTA_1") (pintype "output"))
      (node (ref "U21") (pin "2") (pinfunction "INA-_2") (pintype "input"))
    )
    (net (code "50") (name "Net-(U21-INB+)") (class "Default")
      (node (ref "C27") (pin "2") (pinfunction "2_2") (pintype "passive"))
      (node (ref "L10") (pin "1") (pinfunction "1_1") (pintype "passive"))
      (node (ref "L9") (pin "2") (pinfunction "2_2") (pintype "passive"))
      (node (ref "U21") (pin "5") (pinfunction "INB+_5") (pintype "input"))
    )
    (net (code "51") (name "Net-(U21-INB-)") (class "Default")
      (node (ref "R104") (pin "1") (pinfunction "1_1") (pintype "passive"))
      (node (ref "U21") (pin "6") (pinfunction "INB-_6") (pintype "input"))
      (node (ref "U21") (pin "7") (pinfunction "OUTB_7") (pintype "output"))
    )
    (net (code "52") (name "Net-(U22-INA+)") (class "Default")
      (node (ref "C32") (pin "2") (pinfunction "2_2") (pintype "passive"))
      (node (ref "L14") (pin "2") (pinfunction "2_2") (pintype "passive"))
      (node (ref "L15") (pin "1") (pinfunction "1_1") (pintype "passive"))
      (node (ref "U22") (pin "3") (pinfunction "INA+_3") (pintype "input"))
    )
    (net (code "53") (name "Net-(U22-INA-)") (class "Default")
      (node (ref "R107") (pin "1") (pinfunction "1_1") (pintype "passive"))
      (node (ref "U22") (pin "1") (pinfunction "OUTA_1") (pintype "output"))
      (node (ref "U22") (pin "2") (pinfunction "INA-_2") (pintype "input"))
    )
    (net (code "54") (name "Net-(U22-INB+)") (class "Default")
      (node (ref "C30") (pin "2") (pinfunction "2_2") (pintype "passive"))
      (node (ref "L12") (pin "2") (pinfunction "2_2") (pintype "passive"))
      (node (ref "L13") (pin "1") (pinfunction "1_1") (pintype "passive"))
      (node (ref "U22") (pin "5") (pinfunction "INB+_5") (pintype "input"))
    )
    (net (code "55") (name "Net-(U22-INB-)") (class "Default")
      (node (ref "R106") (pin "1") (pinfunction "1_1") (pintype "passive"))
      (node (ref "U22") (pin "6") (pinfunction "INB-_6") (pintype "input"))
      (node (ref "U22") (pin "7") (pinfunction "OUTB_7") (pintype "output"))
    )
    (net (code "56") (name "Net-(U23-INA+)") (class "Default")
      (node (ref "C37") (pin "2") (pinfunction "2_2") (pintype "passive"))
      (node (ref "L19") (pin "2") (pinfunction "2_2") (pintype "passive"))
      (node (ref "L20") (pin "1") (pinfunction "1_1") (pintype "passive"))
      (node (ref "U23") (pin "3") (pinfunction "INA+_3") (pintype "input"))
    )
    (net (code "57") (name "Net-(U23-INA-)") (class "Default")
      (node (ref "R109") (pin "1") (pinfunction "1_1") (pintype "passive"))
      (node (ref "U23") (pin "1") (pinfunction "OUTA_1") (pintype "output"))
      (node (ref "U23") (pin "2") (pinfunction "INA-_2") (pintype "input"))
    )
    (net (code "58") (name "Net-(U23-INB+)") (class "Default")
      (node (ref "C34") (pin "2") (pinfunction "2_2") (pintype "passive"))
      (node (ref "L16") (pin "2") (pinfunction "2_2") (pintype "passive"))
      (node (ref "L17") (pin "1") (pinfunction "1_1") (pintype "passive"))
      (node (ref "U23") (pin "5") (pinfunction "INB+_5") (pintype "input"))
    )
    (net (code "59") (name "Net-(U23-INB-)") (class "Default")
      (node (ref "R108") (pin "1") (pinfunction "1_1") (pintype "passive"))
      (node (ref "U23") (pin "6") (pinfunction "INB-_6") (pintype "input"))
      (node (ref "U23") (pin "7") (pinfunction "OUTB_7") (pintype "output"))
    )
    (net (code "60") (name "Net-(U24-INA+)") (class "Default")
      (node (ref "C42") (pin "2") (pinfunction "2_2") (pintype "passive"))
      (node (ref "L24") (pin "2") (pinfunction "2_2") (pintype "passive"))
      (node (ref "L25") (pin "1") (pinfunction "1_1") (pintype "passive"))
      (node (ref "U24") (pin "3") (pinfunction "INA+_3") (pintype "input"))
    )
    (net (code "61") (name "Net-(U24-INA-)") (class "Default")
      (node (ref "R111") (pin "1") (pinfunction "1_1") (pintype "passive"))
      (node (ref "U24") (pin "1") (pinfunction "OUTA_1") (pintype "output"))
      (node (ref "U24") (pin "2") (pinfunction "INA-_2") (pintype "input"))
    )
    (net (code "62") (name "Net-(U24-INB+)") (class "Default")
      (node (ref "C40") (pin "2") (pinfunction "2_2") (pintype "passive"))
      (node (ref "L22") (pin "2") (pinfunction "2_2") (pintype "passive"))
      (node (ref "L23") (pin "1") (pinfunction "1_1") (pintype "passive"))
      (node (ref "U24") (pin "5") (pinfunction "INB+_5") (pintype "input"))
    )
    (net (code "63") (name "Net-(U24-INB-)") (class "Default")
      (node (ref "R110") (pin "1") (pinfunction "1_1") (pintype "passive"))
      (node (ref "U24") (pin "6") (pinfunction "INB-_6") (pintype "input"))
      (node (ref "U24") (pin "7") (pinfunction "OUTB_7") (pintype "output"))
    )
    (net (code "64") (name "Net-(U25-IN+)") (class "Default")
      (node (ref "C16") (pin "2") (pinfunction "2_2") (pintype "passive"))
      (node (ref "R112") (pin "1") (pinfunction "1_1") (pintype "passive"))
      (node (ref "R114") (pin "2") (pinfunction "2_2") (pintype "passive"))
      (node (ref "U25") (pin "3") (pinfunction "IN+_3") (pintype "input"))
    )
    (net (code "65") (name "Net-(U25-IN-)") (class "Default")
      (node (ref "C14") (pin "1") (pinfunction "1_1") (pintype "passive"))
      (node (ref "C17") (pin "1") (pinfunction "1_1") (pintype "passive"))
      (node (ref "U25") (pin "2") (pinfunction "IN-_2") (pintype "input"))
      (node (ref "U25") (pin "6") (pinfunction "OUT_6") (pintype "output"))
    )
    (net (code "66") (name "VCC") (class "Default")
      (node (ref "C44") (pin "1") (pinfunction "1_1") (pintype "passive"))
      (node (ref "R118") (pin "1") (pinfunction "1_1") (pintype "passive"))
      (node (ref "U18") (pin "8") (pinfunction "V+_8") (pintype "power_in"))
      (node (ref "U19") (pin "8") (pinfunction "V+_8") (pintype "power_in"))
      (node (ref "U20") (pin "8") (pinfunction "V+_8") (pintype "power_in"))
      (node (ref "U21") (pin "8") (pinfunction "V+_8") (pintype "power_in"))
      (node (ref "U22") (pin "8") (pinfunction "V+_8") (pintype "power_in"))
      (node (ref "U23") (pin "8") (pinfunction "V+_8") (pintype "power_in"))
      (node (ref "U24") (pin "8") (pinfunction "V+_8") (pintype "power_in"))
      (node (ref "U25") (pin "7") (pinfunction "V+_7") (pintype "power_in"))
    )
    (net (code "67") (name "unconnected-(U25-NC-Pad8)") (class "Default")
      (node (ref "U25") (pin "8") (pinfunction "NC_8") (pintype "passive"))
    )
    (net (code "68") (name "unconnected-(U25-OS_TRIM-Pad1)") (class "Default")
      (node (ref "U25") (pin "1") (pinfunction "OS_TRIM_1") (pintype "passive"))
    )
    (net (code "69") (name "unconnected-(U25-OS_TRIM-Pad5)") (class "Default")
      (node (ref "U25") (pin "5") (pinfunction "OS_TRIM_5") (pintype "passive"))
    )
  )
)
